# LevelShifter.net
KiCad netlist of a schematic drawn in Altium Designer
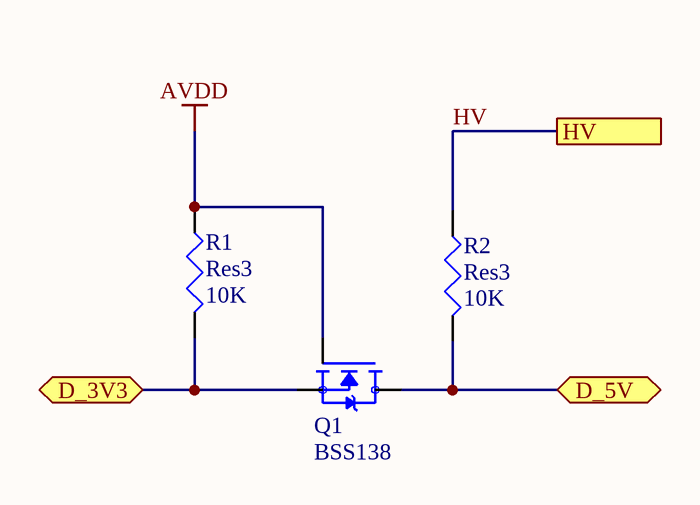
[diagram p0: LevelShifter.SchDoc]

(export (version "E")
  (design (tool "Eeschema 10.0.6"))
  (components
    (comp (ref "Q1")
      (value "BSS138")
      (footprint "SOT95P240X111-3N:SOT95P240X111-3N")
      (description "N-Channel 50V 220mA (Ta) 360mW (Ta) Surface Mount SOT-23-3")
      (fields (field (name "MF") "MICROSS/On Semiconductor"))
      (libsource (lib "BSS138") (part "BSS138"))
    )
    (comp (ref "R1")
      (value "Res3")
      (footprint "J1-0603")
      (description "Resistor")
      (fields (field (name "ALTIUM_VALUE") "10K") (field (name "PUBLISHER") "Altium Limited"))
      (libsource (lib "Miscellaneous Devices") (part "Res3"))
    )
    (comp (ref "R2")
      (value "Res3")
      (footprint "J1-0603")
      (description "Resistor")
      (fields (field (name "ALTIUM_VALUE") "10K") (field (name "PUBLISHER") "Altium Limited"))
      (libsource (lib "Miscellaneous Devices") (part "Res3"))
    )
  )
  (nets
    (net (code "1") (name "/D_3V3") (class "Default")
      (node (ref "Q1") (pin "2") (pinfunction "S_2") (pintype "passive"))
      (node (ref "R1") (pin "2") (pinfunction "2_2") (pintype "passive"))
    )
    (net (code "2") (name "/D_5V") (class "Default")
      (node (ref "Q1") (pin "3") (pinfunction "D_3") (pintype "passive"))
      (node (ref "R2") (pin "2") (pinfunction "2_2") (pintype "passive"))
    )
    (net (code "3") (name "/HV") (class "Default")
      (node (ref "R2") (pin "1") (pinfunction "1_1") (pintype "passive"))
    )
    (net (code "4") (name "AVDD") (class "Default")
      (node (ref "Q1") (pin "1") (pinfunction "G_1") (pintype "passive"))
      (node (ref "R1") (pin "1") (pinfunction "1_1") (pintype "passive"))
    )
  )
)
